# Peripherals.net
KiCad netlist of a schematic drawn in Altium Designer
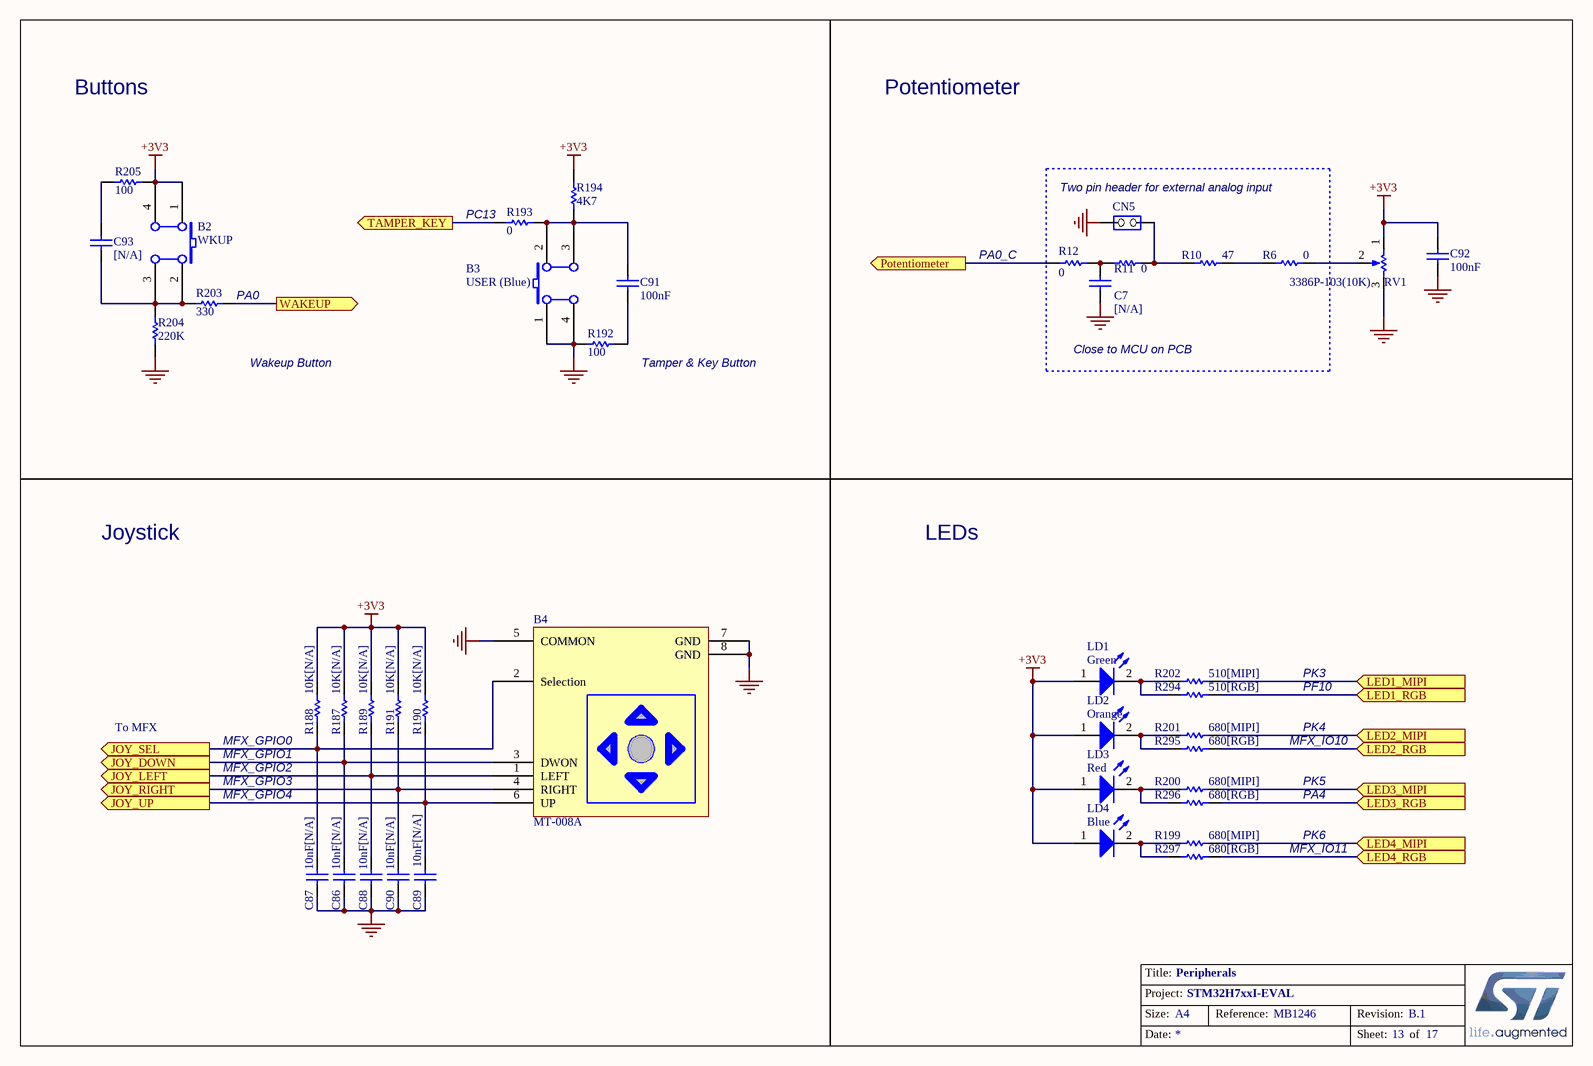
[diagram p0: Peripherals.SchDoc]

(export (version "E")
  (design (tool "Eeschema 10.0.6"))
  (components
    (comp (ref "B2")
      (value "WKUP")
      (footprint "PB10")
      (description "SE PUSHBUTTON")
      (libsource (lib "Documents") (part "SW PUSHBUTTON"))
    )
    (comp (ref "B3")
      (value "USER (Blue)")
      (footprint "PB10")
      (description "SE PUSHBUTTON")
      (libsource (lib "Documents") (part "SW PUSHBUTTON"))
    )
    (comp (ref "B4") (value "MT-008A") (footprint "MT-008A") (libsource (lib "MB1070") (part "MT-008A")))
    (comp (ref "C7")
      (value "[N/A]")
      (footprint "0603C")
      (description "Capacitor")
      (fields (field (name "PUBLISHER") "Altium Limited"))
      (libsource (lib "Miscellaneous Devices") (part "cap"))
    )
    (comp (ref "C86")
      (value "10nF[N/A]")
      (footprint "0603C")
      (description "Capacitor")
      (fields (field (name "PUBLISHER") "Altium Limited"))
      (libsource (lib "Miscellaneous Devices") (part "CAP"))
    )
    (comp (ref "C87")
      (value "10nF[N/A]")
      (footprint "0603C")
      (description "Capacitor")
      (fields (field (name "PUBLISHER") "Altium Limited"))
      (libsource (lib "Miscellaneous Devices") (part "CAP"))
    )
    (comp (ref "C88")
      (value "10nF[N/A]")
      (footprint "0603C")
      (description "Capacitor")
      (fields (field (name "PUBLISHER") "Altium Limited"))
      (libsource (lib "Miscellaneous Devices") (part "CAP"))
    )
    (comp (ref "C89")
      (value "10nF[N/A]")
      (footprint "0603C")
      (description "Capacitor")
      (fields (field (name "PUBLISHER") "Altium Limited"))
      (libsource (lib "Miscellaneous Devices") (part "CAP"))
    )
    (comp (ref "C90")
      (value "10nF[N/A]")
      (footprint "0603C")
      (description "Capacitor")
      (fields (field (name "PUBLISHER") "Altium Limited"))
      (libsource (lib "Miscellaneous Devices") (part "CAP"))
    )
    (comp (ref "C91")
      (value "100nF")
      (footprint "0603C")
      (description "Capacitor")
      (fields (field (name "PUBLISHER") "Altium Limited"))
      (libsource (lib "Miscellaneous Devices") (part "CAP"))
    )
    (comp (ref "C92")
      (value "100nF")
      (footprint "0603C")
      (description "Capacitor")
      (fields (field (name "PUBLISHER") "Altium Limited"))
      (libsource (lib "Miscellaneous Devices") (part "CAP"))
    )
    (comp (ref "C93")
      (value "[N/A]")
      (footprint "0603C")
      (description "Capacitor")
      (fields (field (name "PUBLISHER") "Altium Limited"))
      (libsource (lib "Miscellaneous Devices") (part "CAP"))
    )
    (comp (ref "CN5") (value "~") (footprint "SIP2") (libsource (lib "*") (part "JP2")))
    (comp (ref "LD1")
      (value "Green")
      (footprint "0603D")
      (description "Typical RED, GREEN, YELLOW, AMBER GaAs LED")
      (fields (field (name "PUBLISHER") "Altium Limited"))
      (libsource (lib "Miscellaneous Devices") (part "LED2"))
    )
    (comp (ref "LD2")
      (value "Orange")
      (footprint "0603D")
      (description "Typical RED, GREEN, YELLOW, AMBER GaAs LED")
      (fields (field (name "PUBLISHER") "Altium Limited"))
      (libsource (lib "Miscellaneous Devices") (part "LED2"))
    )
    (comp (ref "LD3")
      (value "Red")
      (footprint "0603D")
      (description "Typical RED, GREEN, YELLOW, AMBER GaAs LED")
      (fields (field (name "PUBLISHER") "Altium Limited"))
      (libsource (lib "Miscellaneous Devices") (part "LED2"))
    )
    (comp (ref "LD4")
      (value "Blue")
      (footprint "0603D")
      (description "Typical RED, GREEN, YELLOW, AMBER GaAs LED")
      (fields (field (name "PUBLISHER") "Altium Limited"))
      (libsource (lib "Miscellaneous Devices") (part "LED2"))
    )
    (comp (ref "R6")
      (value "0")
      (footprint "0603R")
      (description "Resistor")
      (fields (field (name "PUBLISHER") "Altium Limited"))
      (libsource (lib "Miscellaneous Devices") (part "Res1"))
    )
    (comp (ref "R10")
      (value "47")
      (footprint "0603R")
      (description "Resistor")
      (fields (field (name "PUBLISHER") "Altium Limited"))
      (libsource (lib "Miscellaneous Devices") (part "Res1"))
    )
    (comp (ref "R11")
      (value "0")
      (footprint "0603R")
      (description "Resistor")
      (fields (field (name "PUBLISHER") "Altium Limited"))
      (libsource (lib "Miscellaneous Devices") (part "Res1"))
    )
    (comp (ref "R12")
      (value "0")
      (footprint "0603R")
      (description "Resistor")
      (fields (field (name "PUBLISHER") "Altium Limited"))
      (libsource (lib "Miscellaneous Devices") (part "Res1"))
    )
    (comp (ref "R187")
      (value "10K[N/A]")
      (footprint "0603R")
      (description "Resistor")
      (fields (field (name "PUBLISHER") "Altium Limited"))
      (libsource (lib "Miscellaneous Devices") (part "res1"))
    )
    (comp (ref "R188")
      (value "10K[N/A]")
      (footprint "0603R")
      (description "Resistor")
      (fields (field (name "PUBLISHER") "Altium Limited"))
      (libsource (lib "Miscellaneous Devices") (part "res1"))
    )
    (comp (ref "R189")
      (value "10K[N/A]")
      (footprint "0603R")
      (description "Resistor")
      (fields (field (name "PUBLISHER") "Altium Limited"))
      (libsource (lib "Miscellaneous Devices") (part "res1"))
    )
    (comp (ref "R190")
      (value "10K[N/A]")
      (footprint "0603R")
      (description "Resistor")
      (fields (field (name "PUBLISHER") "Altium Limited"))
      (libsource (lib "Miscellaneous Devices") (part "res1"))
    )
    (comp (ref "R191")
      (value "10K[N/A]")
      (footprint "0603R")
      (description "Resistor")
      (fields (field (name "PUBLISHER") "Altium Limited"))
      (libsource (lib "Miscellaneous Devices") (part "res1"))
    )
    (comp (ref "R192")
      (value "100")
      (footprint "0603R")
      (description "Resistor")
      (fields (field (name "PUBLISHER") "Altium Limited"))
      (libsource (lib "Miscellaneous Devices") (part "Res1"))
    )
    (comp (ref "R193")
      (value "0")
      (footprint "0603R")
      (description "Resistor")
      (fields (field (name "PUBLISHER") "Altium Limited"))
      (libsource (lib "Miscellaneous Devices") (part "Res1"))
    )
    (comp (ref "R194")
      (value "4K7")
      (footprint "0603R")
      (description "Resistor")
      (fields (field (name "PUBLISHER") "Altium Limited"))
      (libsource (lib "Miscellaneous Devices") (part "res1"))
    )
    (comp (ref "R199")
      (value "680[MIPI]")
      (footprint "0603R")
      (description "Resistor")
      (fields (field (name "PUBLISHER") "Altium Limited"))
      (libsource (lib "Miscellaneous Devices") (part "Res1"))
    )
    (comp (ref "R200")
      (value "680[MIPI]")
      (footprint "0603R")
      (description "Resistor")
      (fields (field (name "PUBLISHER") "Altium Limited"))
      (libsource (lib "Miscellaneous Devices") (part "Res1"))
    )
    (comp (ref "R201")
      (value "680[MIPI]")
      (footprint "0603R")
      (description "Resistor")
      (fields (field (name "PUBLISHER") "Altium Limited"))
      (libsource (lib "Miscellaneous Devices") (part "Res1"))
    )
    (comp (ref "R202")
      (value "510[MIPI]")
      (footprint "0603R")
      (description "Resistor")
      (fields (field (name "PUBLISHER") "Altium Limited"))
      (libsource (lib "Miscellaneous Devices") (part "Res1"))
    )
    (comp (ref "R203")
      (value "330")
      (footprint "0603R")
      (description "Resistor")
      (fields (field (name "PUBLISHER") "Altium Limited"))
      (libsource (lib "Miscellaneous Devices") (part "Res1"))
    )
    (comp (ref "R204")
      (value "220K")
      (footprint "0603R")
      (description "Resistor")
      (fields (field (name "PUBLISHER") "Altium Limited"))
      (libsource (lib "Miscellaneous Devices") (part "res1"))
    )
    (comp (ref "R205")
      (value "100")
      (footprint "0603R")
      (description "Resistor")
      (fields (field (name "PUBLISHER") "Altium Limited"))
      (libsource (lib "Miscellaneous Devices") (part "Res1"))
    )
    (comp (ref "R294")
      (value "510[RGB]")
      (footprint "0603R")
      (description "Resistor")
      (fields (field (name "PUBLISHER") "Altium Limited"))
      (libsource (lib "Miscellaneous Devices") (part "Res1"))
    )
    (comp (ref "R295")
      (value "680[RGB]")
      (footprint "0603R")
      (description "Resistor")
      (fields (field (name "PUBLISHER") "Altium Limited"))
      (libsource (lib "Miscellaneous Devices") (part "Res1"))
    )
    (comp (ref "R296")
      (value "680[RGB]")
      (footprint "0603R")
      (description "Resistor")
      (fields (field (name "PUBLISHER") "Altium Limited"))
      (libsource (lib "Miscellaneous Devices") (part "Res1"))
    )
    (comp (ref "R297")
      (value "680[RGB]")
      (footprint "0603R")
      (description "Resistor")
      (fields (field (name "PUBLISHER") "Altium Limited"))
      (libsource (lib "Miscellaneous Devices") (part "Res1"))
    )
    (comp (ref "RV1")
      (value "3386P-103(10K)")
      (footprint "3386P")
      (libsource (lib "STR910_SCHLIB") (part "RV"))
    )
  )
  (nets
    (net (code "1") (name "+3V3") (class "Default")
      (node (ref "B2") (pin "1") (pinfunction "A0_1") (pintype "passive"))
      (node (ref "B2") (pin "4") (pinfunction "A1_4") (pintype "passive"))
      (node (ref "C92") (pin "1") (pinfunction "1_1") (pintype "passive"))
      (node (ref "LD1") (pin "1") (pinfunction "A_1") (pintype "passive"))
      (node (ref "LD2") (pin "1") (pinfunction "A_1") (pintype "passive"))
      (node (ref "LD3") (pin "1") (pinfunction "A_1") (pintype "passive"))
      (node (ref "LD4") (pin "1") (pinfunction "A_1") (pintype "passive"))
      (node (ref "R187") (pin "1") (pinfunction "1_1") (pintype "passive"))
      (node (ref "R188") (pin "1") (pinfunction "1_1") (pintype "passive"))
      (node (ref "R189") (pin "1") (pinfunction "1_1") (pintype "passive"))
      (node (ref "R190") (pin "1") (pinfunction "1_1") (pintype "passive"))
      (node (ref "R191") (pin "1") (pinfunction "1_1") (pintype "passive"))
      (node (ref "R194") (pin "2") (pinfunction "2_2") (pintype "passive"))
      (node (ref "R205") (pin "1") (pinfunction "1_1") (pintype "passive"))
      (node (ref "RV1") (pin "1") (pinfunction "BOT_1") (pintype "passive"))
    )
    (net (code "2") (name "/JOY_DOWN") (class "Default")
      (node (ref "B4") (pin "3") (pinfunction "DWON_3") (pintype "passive"))
      (node (ref "C86") (pin "2") (pinfunction "2_2") (pintype "passive"))
      (node (ref "R187") (pin "2") (pinfunction "2_2") (pintype "passive"))
    )
    (net (code "3") (name "/JOY_LEFT") (class "Default")
      (node (ref "B4") (pin "1") (pinfunction "LEFT_1") (pintype "passive"))
      (node (ref "C88") (pin "2") (pinfunction "2_2") (pintype "passive"))
      (node (ref "R189") (pin "2") (pinfunction "2_2") (pintype "passive"))
    )
    (net (code "4") (name "/JOY_RIGHT") (class "Default")
      (node (ref "B4") (pin "4") (pinfunction "RIGHT_4") (pintype "passive"))
      (node (ref "C90") (pin "2") (pinfunction "2_2") (pintype "passive"))
      (node (ref "R191") (pin "2") (pinfunction "2_2") (pintype "passive"))
    )
    (net (code "5") (name "/JOY_SEL") (class "Default")
      (node (ref "B4") (pin "2") (pinfunction "Selection_2") (pintype "passive"))
      (node (ref "C87") (pin "2") (pinfunction "2_2") (pintype "passive"))
      (node (ref "R188") (pin "2") (pinfunction "2_2") (pintype "passive"))
    )
    (net (code "6") (name "/JOY_UP") (class "Default")
      (node (ref "B4") (pin "6") (pinfunction "UP_6") (pintype "passive"))
      (node (ref "C89") (pin "2") (pinfunction "2_2") (pintype "passive"))
      (node (ref "R190") (pin "2") (pinfunction "2_2") (pintype "passive"))
    )
    (net (code "7") (name "/LED1_MIPI") (class "Default")
      (node (ref "R202") (pin "1") (pinfunction "1_1") (pintype "passive"))
    )
    (net (code "8") (name "/LED1_RGB") (class "Default")
      (node (ref "R294") (pin "1") (pinfunction "1_1") (pintype "passive"))
    )
    (net (code "9") (name "/LED2_MIPI") (class "Default")
      (node (ref "R201") (pin "1") (pinfunction "1_1") (pintype "passive"))
    )
    (net (code "10") (name "/LED2_RGB") (class "Default")
      (node (ref "R295") (pin "1") (pinfunction "1_1") (pintype "passive"))
    )
    (net (code "11") (name "/LED3_MIPI") (class "Default")
      (node (ref "R200") (pin "1") (pinfunction "1_1") (pintype "passive"))
    )
    (net (code "12") (name "/LED3_RGB") (class "Default")
      (node (ref "R296") (pin "1") (pinfunction "1_1") (pintype "passive"))
    )
    (net (code "13") (name "/LED4_MIPI") (class "Default")
      (node (ref "R199") (pin "1") (pinfunction "1_1") (pintype "passive"))
    )
    (net (code "14") (name "/LED4_RGB") (class "Default")
      (node (ref "R297") (pin "1") (pinfunction "1_1") (pintype "passive"))
    )
    (net (code "15") (name "/Potentiometer") (class "Default")
      (node (ref "R12") (pin "2") (pinfunction "2_2") (pintype "passive"))
    )
    (net (code "16") (name "/TAMPER_KEY") (class "Default")
      (node (ref "R193") (pin "2") (pinfunction "2_2") (pintype "passive"))
    )
    (net (code "17") (name "/WAKEUP") (class "Default")
      (node (ref "R203") (pin "2") (pinfunction "2_2") (pintype "passive"))
    )
    (net (code "18") (name "GND") (class "Default")
      (node (ref "B3") (pin "1") (pinfunction "A0_1") (pintype "passive"))
      (node (ref "B3") (pin "4") (pinfunction "A1_4") (pintype "passive"))
      (node (ref "B4") (pin "5") (pinfunction "COMMON_5") (pintype "passive"))
      (node (ref "B4") (pin "7") (pinfunction "GND_7") (pintype "passive"))
      (node (ref "B4") (pin "8") (pinfunction "GND_8") (pintype "passive"))
      (node (ref "C7") (pin "1") (pinfunction "1_1") (pintype "passive"))
      (node (ref "C86") (pin "1") (pinfunction "1_1") (pintype "passive"))
      (node (ref "C87") (pin "1") (pinfunction "1_1") (pintype "passive"))
      (node (ref "C88") (pin "1") (pinfunction "1_1") (pintype "passive"))
      (node (ref "C89") (pin "1") (pinfunction "1_1") (pintype "passive"))
      (node (ref "C90") (pin "1") (pinfunction "1_1") (pintype "passive"))
      (node (ref "C92") (pin "2") (pinfunction "2_2") (pintype "passive"))
      (node (ref "CN5") (pin "2") (pinfunction "NO_2") (pintype "passive"))
      (node (ref "R192") (pin "1") (pinfunction "1_1") (pintype "passive"))
      (node (ref "R204") (pin "2") (pinfunction "2_2") (pintype "passive"))
      (node (ref "RV1") (pin "3") (pinfunction "TOP_3") (pintype "passive"))
    )
    (net (code "19") (name "Net-(B2-B0)") (class "Default")
      (node (ref "B2") (pin "2") (pinfunction "B0_2") (pintype "passive"))
      (node (ref "B2") (pin "3") (pinfunction "B1_3") (pintype "passive"))
      (node (ref "C93") (pin "2") (pinfunction "2_2") (pintype "passive"))
      (node (ref "R203") (pin "1") (pinfunction "1_1") (pintype "passive"))
      (node (ref "R204") (pin "1") (pinfunction "1_1") (pintype "passive"))
    )
    (net (code "20") (name "Net-(B3-B0)") (class "Default")
      (node (ref "B3") (pin "2") (pinfunction "B0_2") (pintype "passive"))
      (node (ref "B3") (pin "3") (pinfunction "B1_3") (pintype "passive"))
      (node (ref "C91") (pin "2") (pinfunction "2_2") (pintype "passive"))
      (node (ref "R193") (pin "1") (pinfunction "1_1") (pintype "passive"))
      (node (ref "R194") (pin "1") (pinfunction "1_1") (pintype "passive"))
    )
    (net (code "21") (name "Net-(C7-Pad2)") (class "Default")
      (node (ref "C7") (pin "2") (pinfunction "2_2") (pintype "passive"))
      (node (ref "R11") (pin "1") (pinfunction "1_1") (pintype "passive"))
      (node (ref "R12") (pin "1") (pinfunction "1_1") (pintype "passive"))
    )
    (net (code "22") (name "Net-(C91-Pad1)") (class "Default")
      (node (ref "C91") (pin "1") (pinfunction "1_1") (pintype "passive"))
      (node (ref "R192") (pin "2") (pinfunction "2_2") (pintype "passive"))
    )
    (net (code "23") (name "Net-(C93-Pad1)") (class "Default")
      (node (ref "C93") (pin "1") (pinfunction "1_1") (pintype "passive"))
      (node (ref "R205") (pin "2") (pinfunction "2_2") (pintype "passive"))
    )
    (net (code "24") (name "Net-(CN5-COMMON)") (class "Default")
      (node (ref "CN5") (pin "1") (pinfunction "COMMON_1") (pintype "passive"))
      (node (ref "R10") (pin "1") (pinfunction "1_1") (pintype "passive"))
      (node (ref "R11") (pin "2") (pinfunction "2_2") (pintype "passive"))
    )
    (net (code "25") (name "Net-(LD1-K)") (class "Default")
      (node (ref "LD1") (pin "2") (pinfunction "K_2") (pintype "passive"))
      (node (ref "R202") (pin "2") (pinfunction "2_2") (pintype "passive"))
      (node (ref "R294") (pin "2") (pinfunction "2_2") (pintype "passive"))
    )
    (net (code "26") (name "Net-(LD2-K)") (class "Default")
      (node (ref "LD2") (pin "2") (pinfunction "K_2") (pintype "passive"))
      (node (ref "R201") (pin "2") (pinfunction "2_2") (pintype "passive"))
      (node (ref "R295") (pin "2") (pinfunction "2_2") (pintype "passive"))
    )
    (net (code "27") (name "Net-(LD3-K)") (class "Default")
      (node (ref "LD3") (pin "2") (pinfunction "K_2") (pintype "passive"))
      (node (ref "R200") (pin "2") (pinfunction "2_2") (pintype "passive"))
      (node (ref "R296") (pin "2") (pinfunction "2_2") (pintype "passive"))
    )
    (net (code "28") (name "Net-(LD4-K)") (class "Default")
      (node (ref "LD4") (pin "2") (pinfunction "K_2") (pintype "passive"))
      (node (ref "R199") (pin "2") (pinfunction "2_2") (pintype "passive"))
      (node (ref "R297") (pin "2") (pinfunction "2_2") (pintype "passive"))
    )
    (net (code "29") (name "Net-(R10-Pad2)") (class "Default")
      (node (ref "R10") (pin "2") (pinfunction "2_2") (pintype "passive"))
      (node (ref "R6") (pin "1") (pinfunction "1_1") (pintype "passive"))
    )
    (net (code "30") (name "Net-(RV1-TAP)") (class "Default")
      (node (ref "R6") (pin "2") (pinfunction "2_2") (pintype "passive"))
      (node (ref "RV1") (pin "2") (pinfunction "TAP_2") (pintype "passive"))
    )
  )
)
